# semafor-a-r2.net
KiCad netlist of a schematic drawn in EAGLE
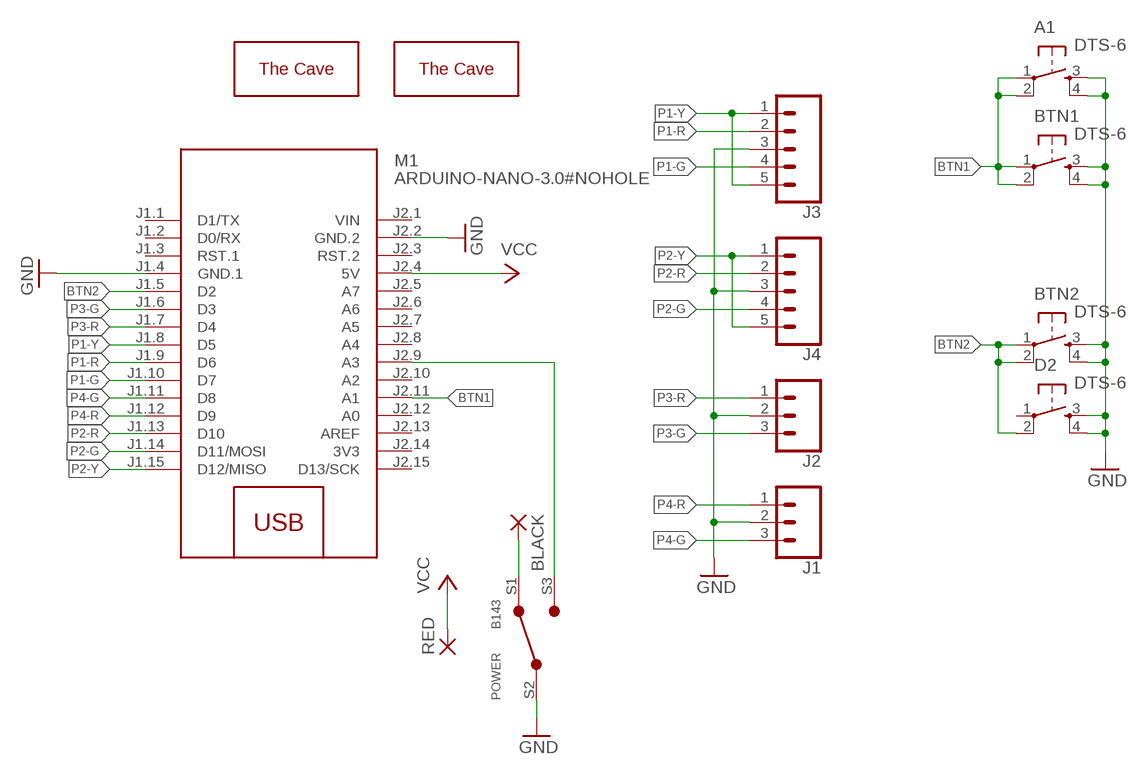
[diagram p0: schematic, sheet 1]

(export (version "E")
  (design (tool "Eeschema 10.0.6"))
  (components
    (comp (ref "A1")
      (value "DTS-6")
      (footprint "eagle-import:DTS-6")
      (libsource (lib "eagle-import") (part "DTS-6"))
    )
    (comp (ref "BLACK")
      (value "WIREPAD2,54/1,0")
      (footprint "eagle-import:2,54_1,0")
      (libsource (lib "eagle-import") (part "WIREPAD2,54/1,0"))
    )
    (comp (ref "BTN1")
      (value "DTS-6")
      (footprint "eagle-import:DTS-6")
      (libsource (lib "eagle-import") (part "DTS-6"))
    )
    (comp (ref "BTN2")
      (value "DTS-6")
      (footprint "eagle-import:DTS-6")
      (libsource (lib "eagle-import") (part "DTS-6"))
    )
    (comp (ref "D2")
      (value "DTS-6")
      (footprint "eagle-import:DTS-6")
      (libsource (lib "eagle-import") (part "DTS-6"))
    )
    (comp (ref "J1")
      (value "CONN_031X03_NO_SILK")
      (footprint "eagle-import:1X03_NO_SILK")
      (libsource (lib "eagle-import") (part "CONN_031X03_NO_SILK"))
    )
    (comp (ref "J2")
      (value "CONN_031X03_NO_SILK")
      (footprint "eagle-import:1X03_NO_SILK")
      (libsource (lib "eagle-import") (part "CONN_031X03_NO_SILK"))
    )
    (comp (ref "J3")
      (value "CONN_05NO_SILK")
      (footprint "eagle-import:1X05_NO_SILK")
      (libsource (lib "eagle-import") (part "CONN_05NO_SILK"))
    )
    (comp (ref "J4")
      (value "CONN_05NO_SILK")
      (footprint "eagle-import:1X05_NO_SILK")
      (libsource (lib "eagle-import") (part "CONN_05NO_SILK"))
    )
    (comp (ref "M1")
      (value "ARDUINO-NANO-3.0#NOHOLE")
      (footprint "eagle-import:ARDUINO-NANO-3.0")
      (libsource (lib "eagle-import") (part "ARDUINO-NANO-3.0#NOHOLE"))
    )
    (comp (ref "POWER")
      (value "B143")
      (footprint "eagle-import:B143")
      (libsource (lib "eagle-import") (part "B143"))
    )
    (comp (ref "RED")
      (value "WIREPAD2,54/1,0")
      (footprint "eagle-import:2,54_1,0")
      (libsource (lib "eagle-import") (part "WIREPAD2,54/1,0"))
    )
    (comp (ref "U$1")
      (value "THECAVE_LOGO_NEW_TOP_SMALL")
      (footprint "eagle-import:NEW_LOGO_SMALL_TOP")
      (libsource (lib "eagle-import") (part "THECAVE_LOGO_NEW_TOP_SMALL"))
    )
    (comp (ref "U$2")
      (value "THECAVE_LOGO_NEW_BOTTOM")
      (footprint "eagle-import:NEW_LOGO_BOTTOM")
      (libsource (lib "eagle-import") (part "THECAVE_LOGO_NEW_BOTTOM"))
    )
  )
  (nets
    (net (code "1") (name "/3V3") (class "Default")
      (node (ref "M1") (pin "J2.14") (pinfunction "3V3_J2.14") (pintype "power_in"))
    )
    (net (code "2") (name "/VIN") (class "Default")
      (node (ref "M1") (pin "J2.1") (pinfunction "VIN_J2.1") (pintype "power_in"))
    )
    (net (code "3") (name "BTN1") (class "Default")
      (node (ref "A1") (pin "1") (pinfunction "1_1") (pintype "passive"))
      (node (ref "A1") (pin "2") (pinfunction "2_2") (pintype "passive"))
      (node (ref "BTN1") (pin "1") (pinfunction "1_1") (pintype "passive"))
      (node (ref "BTN1") (pin "2") (pinfunction "2_2") (pintype "passive"))
      (node (ref "M1") (pin "J2.11") (pinfunction "A1_J2.11") (pintype "bidirectional"))
    )
    (net (code "4") (name "BTN2") (class "Default")
      (node (ref "BTN2") (pin "1") (pinfunction "1_1") (pintype "passive"))
      (node (ref "BTN2") (pin "2") (pinfunction "2_2") (pintype "passive"))
      (node (ref "D2") (pin "2") (pinfunction "2_2") (pintype "passive"))
      (node (ref "M1") (pin "J1.5") (pinfunction "D2_J1.5") (pintype "bidirectional"))
    )
    (net (code "5") (name "GND") (class "Default")
      (node (ref "A1") (pin "3") (pinfunction "3_3") (pintype "passive"))
      (node (ref "A1") (pin "4") (pinfunction "4_4") (pintype "passive"))
      (node (ref "BTN1") (pin "3") (pinfunction "3_3") (pintype "passive"))
      (node (ref "BTN1") (pin "4") (pinfunction "4_4") (pintype "passive"))
      (node (ref "BTN2") (pin "3") (pinfunction "3_3") (pintype "passive"))
      (node (ref "BTN2") (pin "4") (pinfunction "4_4") (pintype "passive"))
      (node (ref "D2") (pin "3") (pinfunction "3_3") (pintype "passive"))
      (node (ref "D2") (pin "4") (pinfunction "4_4") (pintype "passive"))
      (node (ref "J1") (pin "2") (pinfunction "2_2") (pintype "passive"))
      (node (ref "J2") (pin "2") (pinfunction "2_2") (pintype "passive"))
      (node (ref "J3") (pin "3") (pinfunction "3_3") (pintype "passive"))
      (node (ref "J4") (pin "3") (pinfunction "3_3") (pintype "passive"))
      (node (ref "M1") (pin "J1.4") (pinfunction "GND.1_J1.4") (pintype "power_in"))
      (node (ref "M1") (pin "J2.2") (pinfunction "GND.2_J2.2") (pintype "power_in"))
      (node (ref "POWER") (pin "S2") (pinfunction "COM_S2") (pintype "bidirectional"))
    )
    (net (code "6") (name "Net-(BLACK-P)") (class "Default")
      (node (ref "BLACK") (pin "1") (pinfunction "P_1") (pintype "passive"))
      (node (ref "POWER") (pin "S1") (pinfunction "S1_S1") (pintype "bidirectional"))
    )
    (net (code "7") (name "Net-(M1-A3)") (class "Default")
      (node (ref "M1") (pin "J2.9") (pinfunction "A3_J2.9") (pintype "bidirectional"))
      (node (ref "POWER") (pin "S3") (pinfunction "S2_S3") (pintype "bidirectional"))
    )
    (net (code "8") (name "P1-G") (class "Default")
      (node (ref "J3") (pin "4") (pinfunction "4_4") (pintype "passive"))
      (node (ref "M1") (pin "J1.10") (pinfunction "D7_J1.10") (pintype "bidirectional"))
    )
    (net (code "9") (name "P1-R") (class "Default")
      (node (ref "J3") (pin "2") (pinfunction "2_2") (pintype "passive"))
      (node (ref "M1") (pin "J1.9") (pinfunction "D6_J1.9") (pintype "bidirectional"))
    )
    (net (code "10") (name "P1-Y") (class "Default")
      (node (ref "J3") (pin "1") (pinfunction "1_1") (pintype "passive"))
      (node (ref "J3") (pin "5") (pinfunction "5_5") (pintype "passive"))
      (node (ref "M1") (pin "J1.8") (pinfunction "D5_J1.8") (pintype "bidirectional"))
    )
    (net (code "11") (name "P2-G") (class "Default")
      (node (ref "J4") (pin "4") (pinfunction "4_4") (pintype "passive"))
      (node (ref "M1") (pin "J1.14") (pinfunction "D11/MOSI_J1.14") (pintype "bidirectional"))
    )
    (net (code "12") (name "P2-R") (class "Default")
      (node (ref "J4") (pin "2") (pinfunction "2_2") (pintype "passive"))
      (node (ref "M1") (pin "J1.13") (pinfunction "D10_J1.13") (pintype "bidirectional"))
    )
    (net (code "13") (name "P2-Y") (class "Default")
      (node (ref "J4") (pin "1") (pinfunction "1_1") (pintype "passive"))
      (node (ref "J4") (pin "5") (pinfunction "5_5") (pintype "passive"))
      (node (ref "M1") (pin "J1.15") (pinfunction "D12/MISO_J1.15") (pintype "bidirectional"))
    )
    (net (code "14") (name "P3-G") (class "Default")
      (node (ref "J2") (pin "3") (pinfunction "3_3") (pintype "passive"))
      (node (ref "M1") (pin "J1.6") (pinfunction "D3_J1.6") (pintype "bidirectional"))
    )
    (net (code "15") (name "P3-R") (class "Default")
      (node (ref "J2") (pin "1") (pinfunction "1_1") (pintype "passive"))
      (node (ref "M1") (pin "J1.7") (pinfunction "D4_J1.7") (pintype "bidirectional"))
    )
    (net (code "16") (name "P4-G") (class "Default")
      (node (ref "J1") (pin "3") (pinfunction "3_3") (pintype "passive"))
      (node (ref "M1") (pin "J1.11") (pinfunction "D8_J1.11") (pintype "bidirectional"))
    )
    (net (code "17") (name "P4-R") (class "Default")
      (node (ref "J1") (pin "1") (pinfunction "1_1") (pintype "passive"))
      (node (ref "M1") (pin "J1.12") (pinfunction "D9_J1.12") (pintype "bidirectional"))
    )
    (net (code "18") (name "VCC") (class "Default")
      (node (ref "M1") (pin "J2.4") (pinfunction "5V_J2.4") (pintype "power_in"))
      (node (ref "RED") (pin "1") (pinfunction "P_1") (pintype "passive"))
    )
    (net (code "19") (name "unconnected-(D2-Pad1)") (class "Default")
      (node (ref "D2") (pin "1") (pinfunction "1_1") (pintype "passive"))
    )
    (net (code "20") (name "unconnected-(M1-A0-PadJ2.12)") (class "Default")
      (node (ref "M1") (pin "J2.12") (pinfunction "A0_J2.12") (pintype "bidirectional"))
    )
    (net (code "21") (name "unconnected-(M1-A2-PadJ2.10)") (class "Default")
      (node (ref "M1") (pin "J2.10") (pinfunction "A2_J2.10") (pintype "bidirectional"))
    )
    (net (code "22") (name "unconnected-(M1-A4-PadJ2.8)") (class "Default")
      (node (ref "M1") (pin "J2.8") (pinfunction "A4_J2.8") (pintype "bidirectional"))
    )
    (net (code "23") (name "unconnected-(M1-A5-PadJ2.7)") (class "Default")
      (node (ref "M1") (pin "J2.7") (pinfunction "A5_J2.7") (pintype "bidirectional"))
    )
    (net (code "24") (name "unconnected-(M1-A6-PadJ2.6)") (class "Default")
      (node (ref "M1") (pin "J2.6") (pinfunction "A6_J2.6") (pintype "bidirectional"))
    )
    (net (code "25") (name "unconnected-(M1-A7-PadJ2.5)") (class "Default")
      (node (ref "M1") (pin "J2.5") (pinfunction "A7_J2.5") (pintype "bidirectional"))
    )
    (net (code "26") (name "unconnected-(M1-AREF-PadJ2.13)") (class "Default")
      (node (ref "M1") (pin "J2.13") (pinfunction "AREF_J2.13") (pintype "bidirectional"))
    )
    (net (code "27") (name "unconnected-(M1-D0{slash}RX-PadJ1.2)") (class "Default")
      (node (ref "M1") (pin "J1.2") (pinfunction "D0/RX_J1.2") (pintype "bidirectional"))
    )
    (net (code "28") (name "unconnected-(M1-D1{slash}TX-PadJ1.1)") (class "Default")
      (node (ref "M1") (pin "J1.1") (pinfunction "D1/TX_J1.1") (pintype "bidirectional"))
    )
    (net (code "29") (name "unconnected-(M1-D13{slash}SCK-PadJ2.15)") (class "Default")
      (node (ref "M1") (pin "J2.15") (pinfunction "D13/SCK_J2.15") (pintype "bidirectional"))
    )
    (net (code "30") (name "unconnected-(M1-RST.1-PadJ1.3)") (class "Default")
      (node (ref "M1") (pin "J1.3") (pinfunction "RST.1_J1.3") (pintype "bidirectional"))
    )
    (net (code "31") (name "unconnected-(M1-RST.2-PadJ2.3)") (class "Default")
      (node (ref "M1") (pin "J2.3") (pinfunction "RST.2_J2.3") (pintype "bidirectional"))
    )
  )
)
